# tanekonsat2022_auto_schematic.net
KiCad netlist of a schematic drawn in Altium Designer
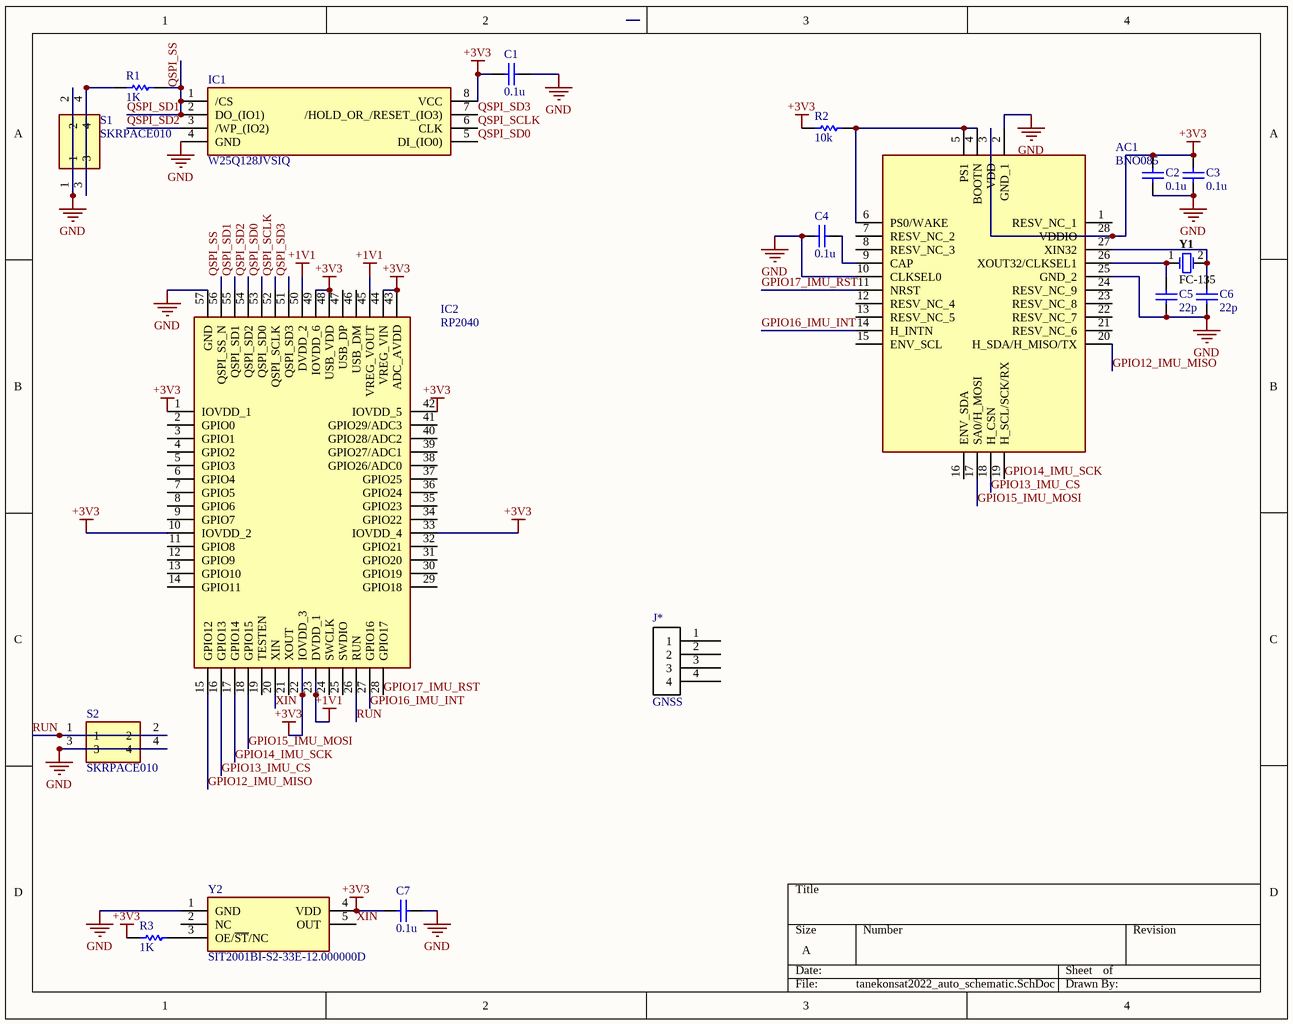
[diagram p0: tanekonsat2022_auto_schematic.SchDoc]

(export (version "E")
  (design (tool "Eeschema 10.0.6"))
  (components
    (comp (ref "AC1")
      (value "BNO085")
      (footprint "SamacSys:BNO085")
      (description "Accelerometer")
      (libsource (lib "*") (part "BNO085"))
    )
    (comp (ref "C1")
      (value "0.1u")
      (footprint "1608[0603]")
      (description "Capacitor")
      (libsource (lib "Simulation Generic Components") (part "Capacitor"))
    )
    (comp (ref "C2")
      (value "0.1u")
      (footprint "1608[0603]")
      (description "Capacitor")
      (libsource (lib "Simulation Generic Components") (part "Capacitor"))
    )
    (comp (ref "C3")
      (value "0.1u")
      (footprint "1608[0603]")
      (description "Capacitor")
      (libsource (lib "Simulation Generic Components") (part "Capacitor"))
    )
    (comp (ref "C4")
      (value "0.1u")
      (footprint "1608[0603]")
      (description "Capacitor")
      (libsource (lib "Simulation Generic Components") (part "Capacitor"))
    )
    (comp (ref "C5")
      (value "22p")
      (footprint "1608[0603]")
      (description "Capacitor")
      (libsource (lib "Simulation Generic Components") (part "Capacitor"))
    )
    (comp (ref "C6")
      (value "22p")
      (footprint "1608[0603]")
      (description "Capacitor")
      (libsource (lib "Simulation Generic Components") (part "Capacitor"))
    )
    (comp (ref "C7")
      (value "0.1u")
      (footprint "1608[0603]")
      (description "Capacitor")
      (libsource (lib "Simulation Generic Components") (part "Capacitor"))
    )
    (comp (ref "IC1")
      (value "W25Q128JVSIQ")
      (footprint "SamacSys:SOIC127P790X216-8N")
      (description "Integrated Circuit")
      (fields (field (name "MOUSER PART NUMBER") "454-W25Q128JVSIQ"))
      (libsource (lib "*") (part "W25Q128JVSIQ"))
    )
    (comp (ref "IC2")
      (value "RP2040")
      (footprint "SamacSys:QFN40P700X700X90-57N-D")
      (description "Integrated Circuit")
      (libsource (lib "*") (part "RP2040"))
    )
    (comp (ref "J*") (value "GNSS") (libsource (lib "tanekonsat_lib") (part "PinHeader_1.27_4_Half")))
    (comp (ref "R1")
      (value "1K")
      (footprint "1608[0603]")
      (description "Resistor")
      (libsource (lib "Simulation Generic Components") (part "Resistor"))
    )
    (comp (ref "R2")
      (value "10k")
      (footprint "1608[0603]")
      (description "Resistor")
      (libsource (lib "Simulation Generic Components") (part "Resistor"))
    )
    (comp (ref "R3")
      (value "1K")
      (footprint "1608[0603]")
      (description "Resistor")
      (libsource (lib "Simulation Generic Components") (part "Resistor"))
    )
    (comp (ref "S1")
      (value "SKRPACE010")
      (footprint "SamacSys:SMT(4.2X3.2)")
      (description "Switch")
      (fields (field (name "MOUSER PART NUMBER") "688-SKRPACE010"))
      (libsource (lib "*") (part "SKRPACE010"))
    )
    (comp (ref "S2")
      (value "SKRPACE010")
      (footprint "SamacSys:SMT(4.2X3.2)")
      (description "Switch")
      (fields (field (name "MOUSER PART NUMBER") "688-SKRPACE010"))
      (libsource (lib "") (part "SKRPACE010_1"))
    )
    (comp (ref "Y1")
      (value "FC-135")
      (footprint "EPSON-FC-135_V")
      (description "Crystal Unit, 32 to 77.5 KHz, 0.5 uW, -40 to 85 degC, 2-Pin SMD, RoHS")
      (fields (field (name "MANUFACTURER") "Epson"))
      (libsource (lib "Altium Content Vault") (part "XTAL-1-2-2"))
    )
    (comp (ref "Y2")
      (value "SIT2001BI-S2-33E-12.000000D")
      (footprint "SamacSys:SOT95P280X145-5N")
      (description "Crystal or Oscillator")
      (libsource (lib "*") (part "SIT2001BI-S2-33E-12.000000D"))
    )
  )
  (nets
    (net (code "1") (name "+1V1") (class "Default")
      (node (ref "IC2") (pin "23") (pinfunction "DVDD_1_23") (pintype "passive"))
      (node (ref "IC2") (pin "45") (pinfunction "VREG_VOUT_45") (pintype "passive"))
      (node (ref "IC2") (pin "50") (pinfunction "DVDD_2_50") (pintype "passive"))
    )
    (net (code "2") (name "+3V3") (class "Default")
      (node (ref "AC1") (pin "28") (pinfunction "VDDIO_28") (pintype "passive"))
      (node (ref "AC1") (pin "3") (pinfunction "VDD_3") (pintype "passive"))
      (node (ref "C1") (pin "1") (pinfunction "1_1") (pintype "passive"))
      (node (ref "C2") (pin "2") (pinfunction "2_2") (pintype "passive"))
      (node (ref "C3") (pin "2") (pinfunction "2_2") (pintype "passive"))
      (node (ref "C7") (pin "1") (pinfunction "1_1") (pintype "passive"))
      (node (ref "IC1") (pin "8") (pinfunction "VCC_8") (pintype "passive"))
      (node (ref "IC2") (pin "1") (pinfunction "IOVDD_1_1") (pintype "passive"))
      (node (ref "IC2") (pin "10") (pinfunction "IOVDD_2_10") (pintype "passive"))
      (node (ref "IC2") (pin "22") (pinfunction "IOVDD_3_22") (pintype "passive"))
      (node (ref "IC2") (pin "33") (pinfunction "IOVDD_4_33") (pintype "passive"))
      (node (ref "IC2") (pin "42") (pinfunction "IOVDD_5_42") (pintype "passive"))
      (node (ref "IC2") (pin "43") (pinfunction "ADC_AVDD_43") (pintype "passive"))
      (node (ref "IC2") (pin "44") (pinfunction "VREG_VIN_44") (pintype "passive"))
      (node (ref "IC2") (pin "48") (pinfunction "USB_VDD_48") (pintype "passive"))
      (node (ref "IC2") (pin "49") (pinfunction "IOVDD_6_49") (pintype "passive"))
      (node (ref "R2") (pin "1") (pinfunction "1_1") (pintype "passive"))
      (node (ref "R3") (pin "1") (pinfunction "1_1") (pintype "passive"))
      (node (ref "Y2") (pin "4") (pinfunction "VDD_4") (pintype "passive"))
    )
    (net (code "3") (name "/GPIO12_IMU_MISO") (class "Default")
      (node (ref "AC1") (pin "20") (pinfunction "H_SDA/H_MISO/TX_20") (pintype "passive"))
      (node (ref "IC2") (pin "15") (pinfunction "GPIO12_15") (pintype "passive"))
    )
    (net (code "4") (name "/GPIO13_IMU_CS") (class "Default")
      (node (ref "AC1") (pin "18") (pinfunction "H_CSN_18") (pintype "passive"))
      (node (ref "IC2") (pin "16") (pinfunction "GPIO13_16") (pintype "passive"))
    )
    (net (code "5") (name "/GPIO14_IMU_SCK") (class "Default")
      (node (ref "AC1") (pin "19") (pinfunction "H_SCL/SCK/RX_19") (pintype "passive"))
      (node (ref "IC2") (pin "17") (pinfunction "GPIO14_17") (pintype "passive"))
    )
    (net (code "6") (name "/GPIO15_IMU_MOSI") (class "Default")
      (node (ref "AC1") (pin "17") (pinfunction "SA0/H_MOSI_17") (pintype "passive"))
      (node (ref "IC2") (pin "18") (pinfunction "GPIO15_18") (pintype "passive"))
    )
    (net (code "7") (name "/GPIO16_IMU_INT") (class "Default")
      (node (ref "AC1") (pin "14") (pinfunction "H_INTN_14") (pintype "passive"))
      (node (ref "IC2") (pin "27") (pinfunction "GPIO16_27") (pintype "passive"))
    )
    (net (code "8") (name "/GPIO17_IMU_RST") (class "Default")
      (node (ref "AC1") (pin "11") (pinfunction "NRST_11") (pintype "passive"))
      (node (ref "IC2") (pin "28") (pinfunction "GPIO17_28") (pintype "passive"))
    )
    (net (code "9") (name "/QSPI_SCLK") (class "Default")
      (node (ref "IC1") (pin "6") (pinfunction "CLK_6") (pintype "passive"))
      (node (ref "IC2") (pin "52") (pinfunction "QSPI_SCLK_52") (pintype "passive"))
    )
    (net (code "10") (name "/QSPI_SD0") (class "Default")
      (node (ref "IC1") (pin "5") (pinfunction "DI_(IO0)_5") (pintype "passive"))
      (node (ref "IC2") (pin "53") (pinfunction "QSPI_SD0_53") (pintype "passive"))
    )
    (net (code "11") (name "/QSPI_SD1") (class "Default")
      (node (ref "IC1") (pin "1") (pinfunction "/CS_1") (pintype "passive"))
      (node (ref "IC1") (pin "2") (pinfunction "DO_(IO1)_2") (pintype "passive"))
      (node (ref "IC2") (pin "55") (pinfunction "QSPI_SD1_55") (pintype "passive"))
      (node (ref "IC2") (pin "56") (pinfunction "QSPI_SS_N_56") (pintype "passive"))
      (node (ref "R1") (pin "2") (pinfunction "2_2") (pintype "passive"))
    )
    (net (code "12") (name "/QSPI_SD2") (class "Default")
      (node (ref "IC1") (pin "3") (pinfunction "/WP_(IO2)_3") (pintype "passive"))
      (node (ref "IC2") (pin "54") (pinfunction "QSPI_SD2_54") (pintype "passive"))
    )
    (net (code "13") (name "/QSPI_SD3") (class "Default")
      (node (ref "IC1") (pin "7") (pinfunction "/HOLD_OR_/RESET_(IO3)_7") (pintype "passive"))
      (node (ref "IC2") (pin "51") (pinfunction "QSPI_SD3_51") (pintype "passive"))
    )
    (net (code "14") (name "/RUN") (class "Default")
      (node (ref "IC2") (pin "26") (pinfunction "RUN_26") (pintype "passive"))
      (node (ref "S2") (pin "1") (pinfunction "1_1") (pintype "passive"))
      (node (ref "S2") (pin "2") (pinfunction "2_2") (pintype "passive"))
    )
    (net (code "15") (name "/XIN") (class "Default")
      (node (ref "IC2") (pin "20") (pinfunction "XIN_20") (pintype "passive"))
      (node (ref "Y2") (pin "5") (pinfunction "OUT_5") (pintype "passive"))
    )
    (net (code "16") (name "GND") (class "Default")
      (node (ref "AC1") (pin "10") (pinfunction "CLKSEL0_10") (pintype "passive"))
      (node (ref "AC1") (pin "2") (pinfunction "GND_1_2") (pintype "passive"))
      (node (ref "AC1") (pin "25") (pinfunction "GND_2_25") (pintype "passive"))
      (node (ref "C1") (pin "2") (pinfunction "2_2") (pintype "passive"))
      (node (ref "C2") (pin "1") (pinfunction "1_1") (pintype "passive"))
      (node (ref "C3") (pin "1") (pinfunction "1_1") (pintype "passive"))
      (node (ref "C4") (pin "1") (pinfunction "1_1") (pintype "passive"))
      (node (ref "C5") (pin "1") (pinfunction "1_1") (pintype "passive"))
      (node (ref "C6") (pin "1") (pinfunction "1_1") (pintype "passive"))
      (node (ref "C7") (pin "2") (pinfunction "2_2") (pintype "passive"))
      (node (ref "IC1") (pin "4") (pinfunction "GND_4") (pintype "passive"))
      (node (ref "IC2") (pin "57") (pinfunction "GND_57") (pintype "passive"))
      (node (ref "S1") (pin "1") (pinfunction "1_1") (pintype "passive"))
      (node (ref "S1") (pin "2") (pinfunction "2_2") (pintype "passive"))
      (node (ref "S2") (pin "3") (pinfunction "3_3") (pintype "passive"))
      (node (ref "S2") (pin "4") (pinfunction "4_4") (pintype "passive"))
      (node (ref "Y2") (pin "1") (pinfunction "GND_1") (pintype "passive"))
    )
    (net (code "17") (name "Net-(AC1-BOOTN)") (class "Default")
      (node (ref "AC1") (pin "4") (pinfunction "BOOTN_4") (pintype "passive"))
      (node (ref "AC1") (pin "5") (pinfunction "PS1_5") (pintype "passive"))
      (node (ref "AC1") (pin "6") (pinfunction "PS0/WAKE_6") (pintype "passive"))
      (node (ref "R2") (pin "2") (pinfunction "2_2") (pintype "passive"))
    )
    (net (code "18") (name "Net-(AC1-CAP)") (class "Default")
      (node (ref "AC1") (pin "9") (pinfunction "CAP_9") (pintype "passive"))
      (node (ref "C4") (pin "2") (pinfunction "2_2") (pintype "passive"))
    )
    (net (code "19") (name "Net-(AC1-XIN32)") (class "Default")
      (node (ref "AC1") (pin "27") (pinfunction "XIN32_27") (pintype "passive"))
      (node (ref "C6") (pin "2") (pinfunction "2_2") (pintype "passive"))
      (node (ref "Y1") (pin "2") (pinfunction "2_2") (pintype "passive"))
    )
    (net (code "20") (name "Net-(AC1-XOUT32{slash}CLKSEL1)") (class "Default")
      (node (ref "AC1") (pin "26") (pinfunction "XOUT32/CLKSEL1_26") (pintype "passive"))
      (node (ref "C5") (pin "2") (pinfunction "2_2") (pintype "passive"))
      (node (ref "Y1") (pin "1") (pinfunction "1_1") (pintype "passive"))
    )
    (net (code "21") (name "Net-(R1-Pad1)") (class "Default")
      (node (ref "R1") (pin "1") (pinfunction "1_1") (pintype "passive"))
      (node (ref "S1") (pin "3") (pinfunction "3_3") (pintype "passive"))
      (node (ref "S1") (pin "4") (pinfunction "4_4") (pintype "passive"))
    )
    (net (code "22") (name "Net-(Y2-OE{slash}~{ST}{slash}NC)") (class "Default")
      (node (ref "R3") (pin "2") (pinfunction "2_2") (pintype "passive"))
      (node (ref "Y2") (pin "3") (pinfunction "OE/~{ST}/NC_3") (pintype "passive"))
    )
    (net (code "23") (name "unconnected-(AC1-ENV_SCL-Pad15)") (class "Default")
      (node (ref "AC1") (pin "15") (pinfunction "ENV_SCL_15") (pintype "passive"))
    )
    (net (code "24") (name "unconnected-(AC1-ENV_SDA-Pad16)") (class "Default")
      (node (ref "AC1") (pin "16") (pinfunction "ENV_SDA_16") (pintype "passive"))
    )
    (net (code "25") (name "unconnected-(AC1-RESV_NC_1-Pad1)") (class "Default")
      (node (ref "AC1") (pin "1") (pinfunction "RESV_NC_1_1") (pintype "passive"))
    )
    (net (code "26") (name "unconnected-(AC1-RESV_NC_2-Pad7)") (class "Default")
      (node (ref "AC1") (pin "7") (pinfunction "RESV_NC_2_7") (pintype "passive"))
    )
    (net (code "27") (name "unconnected-(AC1-RESV_NC_3-Pad8)") (class "Default")
      (node (ref "AC1") (pin "8") (pinfunction "RESV_NC_3_8") (pintype "passive"))
    )
    (net (code "28") (name "unconnected-(AC1-RESV_NC_4-Pad12)") (class "Default")
      (node (ref "AC1") (pin "12") (pinfunction "RESV_NC_4_12") (pintype "passive"))
    )
    (net (code "29") (name "unconnected-(AC1-RESV_NC_5-Pad13)") (class "Default")
      (node (ref "AC1") (pin "13") (pinfunction "RESV_NC_5_13") (pintype "passive"))
    )
    (net (code "30") (name "unconnected-(AC1-RESV_NC_6-Pad21)") (class "Default")
      (node (ref "AC1") (pin "21") (pinfunction "RESV_NC_6_21") (pintype "passive"))
    )
    (net (code "31") (name "unconnected-(AC1-RESV_NC_7-Pad22)") (class "Default")
      (node (ref "AC1") (pin "22") (pinfunction "RESV_NC_7_22") (pintype "passive"))
    )
    (net (code "32") (name "unconnected-(AC1-RESV_NC_8-Pad23)") (class "Default")
      (node (ref "AC1") (pin "23") (pinfunction "RESV_NC_8_23") (pintype "passive"))
    )
    (net (code "33") (name "unconnected-(AC1-RESV_NC_9-Pad24)") (class "Default")
      (node (ref "AC1") (pin "24") (pinfunction "RESV_NC_9_24") (pintype "passive"))
    )
    (net (code "34") (name "unconnected-(IC2-GPIO0-Pad2)") (class "Default")
      (node (ref "IC2") (pin "2") (pinfunction "GPIO0_2") (pintype "passive"))
    )
    (net (code "35") (name "unconnected-(IC2-GPIO1-Pad3)") (class "Default")
      (node (ref "IC2") (pin "3") (pinfunction "GPIO1_3") (pintype "passive"))
    )
    (net (code "36") (name "unconnected-(IC2-GPIO2-Pad4)") (class "Default")
      (node (ref "IC2") (pin "4") (pinfunction "GPIO2_4") (pintype "passive"))
    )
    (net (code "37") (name "unconnected-(IC2-GPIO3-Pad5)") (class "Default")
      (node (ref "IC2") (pin "5") (pinfunction "GPIO3_5") (pintype "passive"))
    )
    (net (code "38") (name "unconnected-(IC2-GPIO4-Pad6)") (class "Default")
      (node (ref "IC2") (pin "6") (pinfunction "GPIO4_6") (pintype "passive"))
    )
    (net (code "39") (name "unconnected-(IC2-GPIO5-Pad7)") (class "Default")
      (node (ref "IC2") (pin "7") (pinfunction "GPIO5_7") (pintype "passive"))
    )
    (net (code "40") (name "unconnected-(IC2-GPIO6-Pad8)") (class "Default")
      (node (ref "IC2") (pin "8") (pinfunction "GPIO6_8") (pintype "passive"))
    )
    (net (code "41") (name "unconnected-(IC2-GPIO7-Pad9)") (class "Default")
      (node (ref "IC2") (pin "9") (pinfunction "GPIO7_9") (pintype "passive"))
    )
    (net (code "42") (name "unconnected-(IC2-GPIO8-Pad11)") (class "Default")
      (node (ref "IC2") (pin "11") (pinfunction "GPIO8_11") (pintype "passive"))
    )
    (net (code "43") (name "unconnected-(IC2-GPIO9-Pad12)") (class "Default")
      (node (ref "IC2") (pin "12") (pinfunction "GPIO9_12") (pintype "passive"))
    )
    (net (code "44") (name "unconnected-(IC2-GPIO10-Pad13)") (class "Default")
      (node (ref "IC2") (pin "13") (pinfunction "GPIO10_13") (pintype "passive"))
    )
    (net (code "45") (name "unconnected-(IC2-GPIO11-Pad14)") (class "Default")
      (node (ref "IC2") (pin "14") (pinfunction "GPIO11_14") (pintype "passive"))
    )
    (net (code "46") (name "unconnected-(IC2-GPIO18-Pad29)") (class "Default")
      (node (ref "IC2") (pin "29") (pinfunction "GPIO18_29") (pintype "passive"))
    )
    (net (code "47") (name "unconnected-(IC2-GPIO19-Pad30)") (class "Default")
      (node (ref "IC2") (pin "30") (pinfunction "GPIO19_30") (pintype "passive"))
    )
    (net (code "48") (name "unconnected-(IC2-GPIO20-Pad31)") (class "Default")
      (node (ref "IC2") (pin "31") (pinfunction "GPIO20_31") (pintype "passive"))
    )
    (net (code "49") (name "unconnected-(IC2-GPIO21-Pad32)") (class "Default")
      (node (ref "IC2") (pin "32") (pinfunction "GPIO21_32") (pintype "passive"))
    )
    (net (code "50") (name "unconnected-(IC2-GPIO22-Pad34)") (class "Default")
      (node (ref "IC2") (pin "34") (pinfunction "GPIO22_34") (pintype "passive"))
    )
    (net (code "51") (name "unconnected-(IC2-GPIO23-Pad35)") (class "Default")
      (node (ref "IC2") (pin "35") (pinfunction "GPIO23_35") (pintype "passive"))
    )
    (net (code "52") (name "unconnected-(IC2-GPIO24-Pad36)") (class "Default")
      (node (ref "IC2") (pin "36") (pinfunction "GPIO24_36") (pintype "passive"))
    )
    (net (code "53") (name "unconnected-(IC2-GPIO25-Pad37)") (class "Default")
      (node (ref "IC2") (pin "37") (pinfunction "GPIO25_37") (pintype "passive"))
    )
    (net (code "54") (name "unconnected-(IC2-GPIO26{slash}ADC0-Pad38)") (class "Default")
      (node (ref "IC2") (pin "38") (pinfunction "GPIO26/ADC0_38") (pintype "passive"))
    )
    (net (code "55") (name "unconnected-(IC2-GPIO27{slash}ADC1-Pad39)") (class "Default")
      (node (ref "IC2") (pin "39") (pinfunction "GPIO27/ADC1_39") (pintype "passive"))
    )
    (net (code "56") (name "unconnected-(IC2-GPIO28{slash}ADC2-Pad40)") (class "Default")
      (node (ref "IC2") (pin "40") (pinfunction "GPIO28/ADC2_40") (pintype "passive"))
    )
    (net (code "57") (name "unconnected-(IC2-GPIO29{slash}ADC3-Pad41)") (class "Default")
      (node (ref "IC2") (pin "41") (pinfunction "GPIO29/ADC3_41") (pintype "passive"))
    )
    (net (code "58") (name "unconnected-(IC2-SWCLK-Pad24)") (class "Default")
      (node (ref "IC2") (pin "24") (pinfunction "SWCLK_24") (pintype "passive"))
    )
    (net (code "59") (name "unconnected-(IC2-SWDIO-Pad25)") (class "Default")
      (node (ref "IC2") (pin "25") (pinfunction "SWDIO_25") (pintype "passive"))
    )
    (net (code "60") (name "unconnected-(IC2-TESTEN-Pad19)") (class "Default")
      (node (ref "IC2") (pin "19") (pinfunction "TESTEN_19") (pintype "passive"))
    )
    (net (code "61") (name "unconnected-(IC2-USB_DM-Pad46)") (class "Default")
      (node (ref "IC2") (pin "46") (pinfunction "USB_DM_46") (pintype "passive"))
    )
    (net (code "62") (name "unconnected-(IC2-USB_DP-Pad47)") (class "Default")
      (node (ref "IC2") (pin "47") (pinfunction "USB_DP_47") (pintype "passive"))
    )
    (net (code "63") (name "unconnected-(IC2-XOUT-Pad21)") (class "Default")
      (node (ref "IC2") (pin "21") (pinfunction "XOUT_21") (pintype "passive"))
    )
    (net (code "64") (name "unconnected-(J*-Pad1)") (class "Default")
      (node (ref "J*") (pin "1") (pinfunction "1_1") (pintype "passive"))
    )
    (net (code "65") (name "unconnected-(J*-Pad2)") (class "Default")
      (node (ref "J*") (pin "2") (pinfunction "2_2") (pintype "passive"))
    )
    (net (code "66") (name "unconnected-(J*-Pad3)") (class "Default")
      (node (ref "J*") (pin "3") (pinfunction "3_3") (pintype "passive"))
    )
    (net (code "67") (name "unconnected-(J*-Pad4)") (class "Default")
      (node (ref "J*") (pin "4") (pinfunction "4_4") (pintype "passive"))
    )
    (net (code "68") (name "unconnected-(Y2-NC-Pad2)") (class "Default")
      (node (ref "Y2") (pin "2") (pinfunction "NC_2") (pintype "passive"))
    )
  )
)
